# Power_Supply.net
KiCad netlist of a schematic drawn in Altium Designer
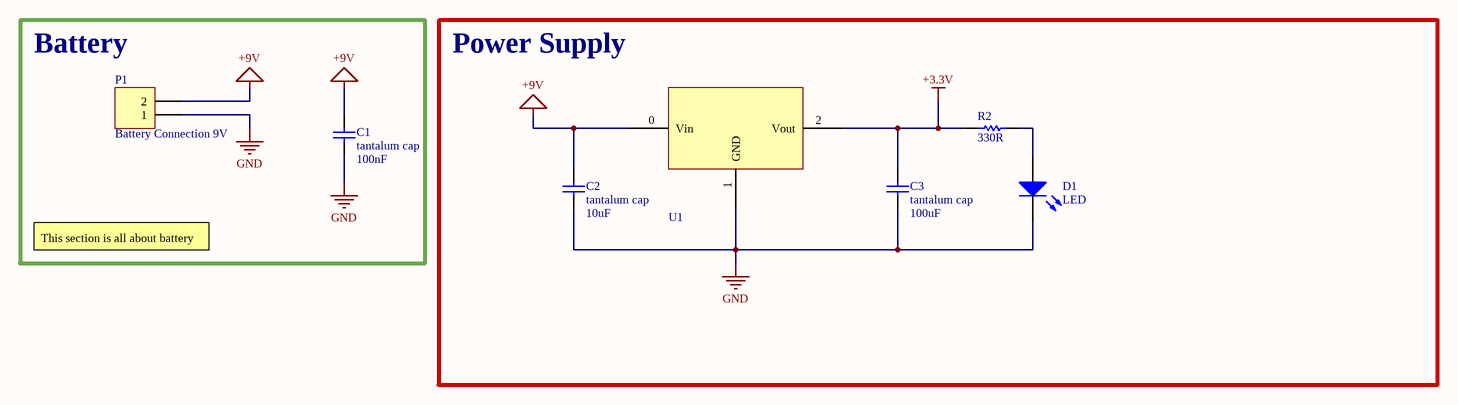
[diagram p0: Power Supply.SchDoc]

(export (version "E")
  (design (tool "Eeschema 10.0.6"))
  (components
    (comp (ref "C1")
      (value "tantalum cap")
      (footprint "C1206tancap")
      (description "Capacitor (Semiconductor SIM Model)")
      (fields (field (name "ALTIUM_VALUE") "100nF") (field (name "PUBLISHER") "Altium Limited"))
      (libsource (lib "MCU_Udemy") (part "Cap Semi_6"))
    )
    (comp (ref "C2")
      (value "tantalum cap")
      (footprint "C1206tancap")
      (description "Capacitor (Semiconductor SIM Model)")
      (fields (field (name "ALTIUM_VALUE") "10uF") (field (name "PUBLISHER") "Altium Limited"))
      (libsource (lib "MCU_Udemy") (part "Cap Semi_6"))
    )
    (comp (ref "C3")
      (value "tantalum cap")
      (footprint "C1206tancap")
      (description "Capacitor (Semiconductor SIM Model)")
      (fields (field (name "ALTIUM_VALUE") "100uF") (field (name "PUBLISHER") "Altium Limited"))
      (libsource (lib "MCU_Udemy") (part "Cap Semi_6"))
    )
    (comp (ref "D1")
      (value "LED")
      (footprint "MY_LED_0805")
      (description "Typical INFRARED GaAs LED")
      (fields (field (name "ASID PART NUMBER") "LED-AS"))
      (libsource (lib "Udemy Library") (part "LED"))
    )
    (comp (ref "P1")
      (value "Battery Connection 9V")
      (footprint "HDR1X2H3dbody")
      (description "Header, 2-Pin, Right Angle")
      (fields (field (name "VOLTAGE") "9V") (field (name "PUBLISHER") "Altium Limited"))
      (libsource (lib "MCU_Udemy") (part "Header 2H"))
    )
    (comp (ref "R2")
      (value "330R")
      (footprint "MY_0805")
      (description "Standard resistor")
      (fields (field (name "ASID PART NUMBER") "Res-AS"))
      (libsource (lib "Udemy Library") (part "Res"))
    )
    (comp (ref "U1") (value "LM1117") (footprint "LM1117") (libsource (lib "PCB Udemy") (part "LM1117")))
  )
  (nets
    (net (code "1") (name "+3.3V") (class "Default")
      (node (ref "C3") (pin "2") (pinfunction "2_2") (pintype "passive"))
      (node (ref "R2") (pin "1") (pinfunction "1_1") (pintype "passive"))
      (node (ref "U1") (pin "2") (pinfunction "Vout_2") (pintype "passive"))
    )
    (net (code "2") (name "+9V") (class "Default")
      (node (ref "C1") (pin "2") (pinfunction "2_2") (pintype "passive"))
      (node (ref "C2") (pin "2") (pinfunction "2_2") (pintype "passive"))
      (node (ref "P1") (pin "2") (pinfunction "2_2") (pintype "passive"))
      (node (ref "U1") (pin "0") (pinfunction "Vin_0") (pintype "passive"))
    )
    (net (code "3") (name "GND") (class "Default")
      (node (ref "C1") (pin "1") (pinfunction "1_1") (pintype "passive"))
      (node (ref "C2") (pin "1") (pinfunction "1_1") (pintype "passive"))
      (node (ref "C3") (pin "1") (pinfunction "1_1") (pintype "passive"))
      (node (ref "D1") (pin "K") (pinfunction "K_K") (pintype "passive"))
      (node (ref "P1") (pin "1") (pinfunction "1_1") (pintype "passive"))
      (node (ref "U1") (pin "1") (pinfunction "GND_1") (pintype "passive"))
    )
    (net (code "4") (name "Net-(D1-PadA)") (class "Default")
      (node (ref "D1") (pin "A") (pinfunction "A_A") (pintype "passive"))
      (node (ref "R2") (pin "2") (pinfunction "2_2") (pintype "passive"))
    )
  )
)
